# layout.net
KiCad netlist of a schematic drawn in EAGLE
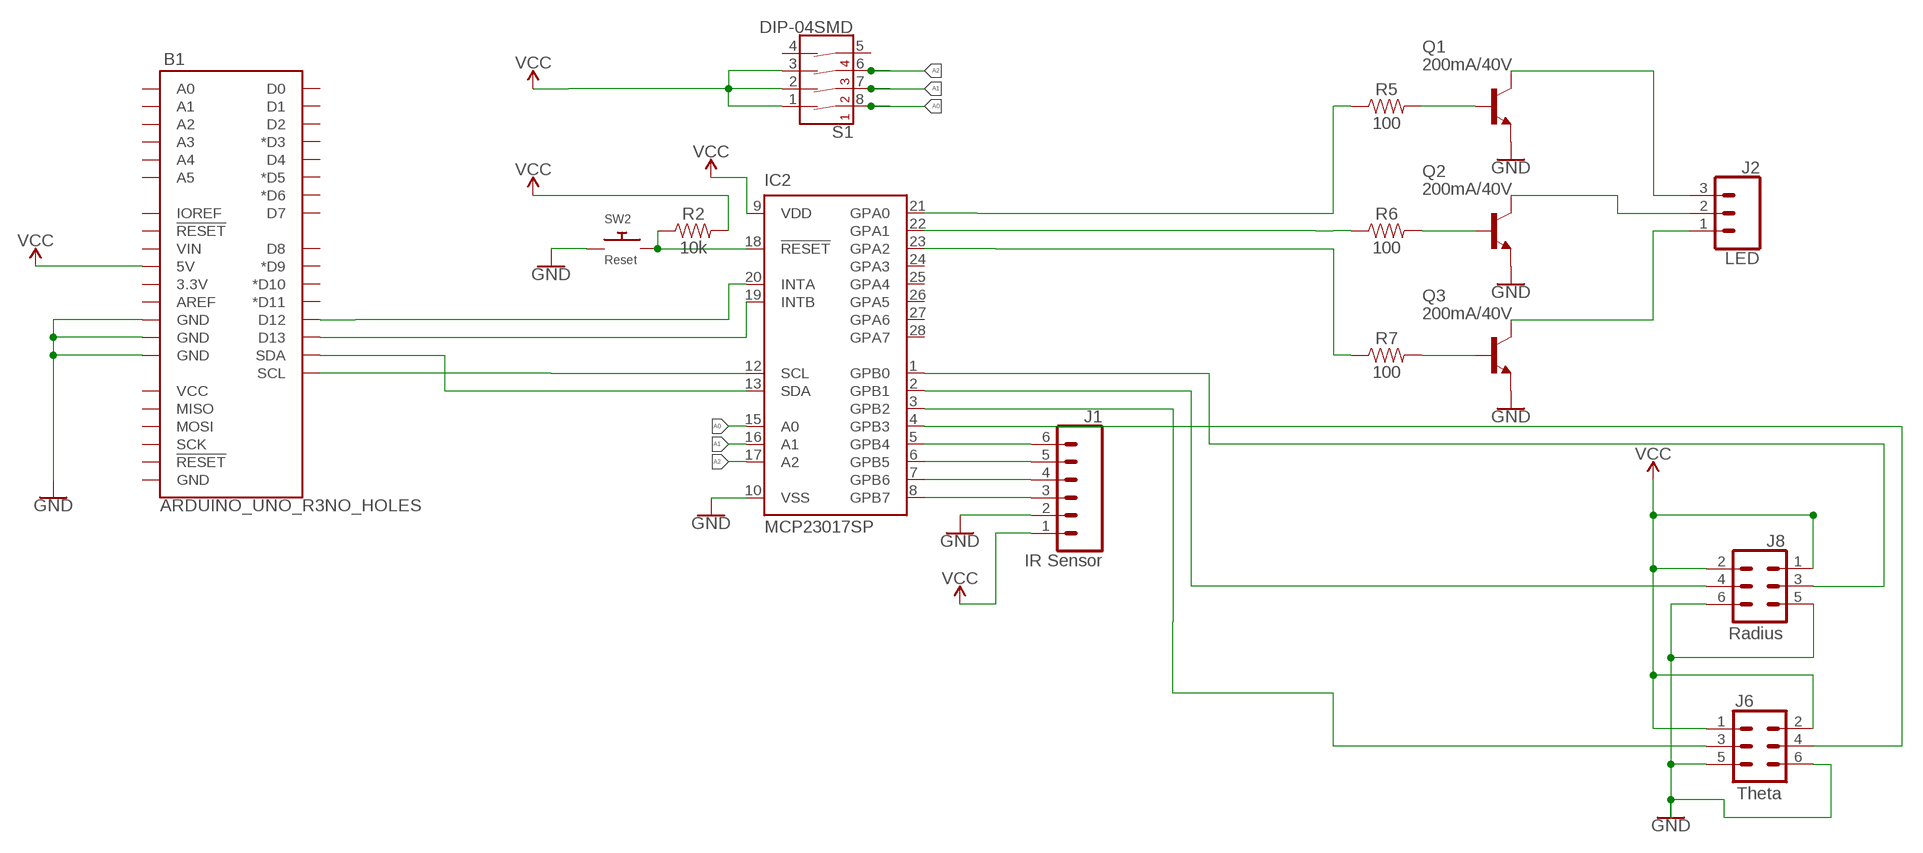
[diagram p0: schematic, sheet 1]

(export (version "E")
  (design (tool "Eeschema 10.0.6"))
  (components
    (comp (ref "B1")
      (value "ARDUINO_UNO_R3NO_HOLES")
      (footprint "eagle-import:ARDUINO_R3_NO_HOLES")
      (libsource (lib "eagle-import") (part "ARDUINO_UNO_R3NO_HOLES"))
    )
    (comp (ref "IC2")
      (value "MCP23017SP")
      (footprint "eagle-import:DIL28-3")
      (libsource (lib "eagle-import") (part "MCP23017SP"))
    )
    (comp (ref "J1")
      (value "IR Sensor")
      (footprint "eagle-import:1X06")
      (libsource (lib "eagle-import") (part "CONN_06SILK_FEMALE_PTH"))
    )
    (comp (ref "J2")
      (value "LED")
      (footprint "eagle-import:1X03")
      (libsource (lib "eagle-import") (part "CONN_03"))
    )
    (comp (ref "J6")
      (value "Theta")
      (footprint "eagle-import:2X3")
      (libsource (lib "eagle-import") (part "CONN_03X22X3_SILK_MALE_PTH"))
    )
    (comp (ref "J8")
      (value "Radius")
      (footprint "eagle-import:2X3")
      (libsource (lib "eagle-import") (part "CONN_03X22X3_SILK_MALE_PTH"))
    )
    (comp (ref "Q1")
      (value "200mA/40V")
      (footprint "eagle-import:TO220")
      (libsource (lib "eagle-import") (part "-NPN-TO220"))
    )
    (comp (ref "Q2")
      (value "200mA/40V")
      (footprint "eagle-import:TO220")
      (libsource (lib "eagle-import") (part "-NPN-TO220"))
    )
    (comp (ref "Q3")
      (value "200mA/40V")
      (footprint "eagle-import:TO220")
      (libsource (lib "eagle-import") (part "-NPN-TO220"))
    )
    (comp (ref "R2")
      (value "10k")
      (footprint "eagle-import:0603")
      (libsource (lib "eagle-import") (part "10KOHM-0603-1/10W-1%"))
    )
    (comp (ref "R5")
      (value "100")
      (footprint "eagle-import:0603")
      (libsource (lib "eagle-import") (part "100OHM-0603-1/4W-5%"))
    )
    (comp (ref "R6")
      (value "100")
      (footprint "eagle-import:0603")
      (libsource (lib "eagle-import") (part "100OHM-0603-1/4W-5%"))
    )
    (comp (ref "R7")
      (value "100")
      (footprint "eagle-import:0603")
      (libsource (lib "eagle-import") (part "100OHM-0603-1/4W-5%"))
    )
    (comp (ref "S1")
      (value "DIP-04SMD")
      (footprint "eagle-import:DIPSWITCH-04-SMD")
      (libsource (lib "eagle-import") (part "DIP-04SMD"))
    )
    (comp (ref "SW2")
      (value "Reset")
      (footprint "eagle-import:BTN_CK_KSS")
      (libsource (lib "eagle-import") (part "SWITCH_PUSHBUTTONC&K_KSS"))
    )
  )
  (nets
    (net (code "1") (name "A0") (class "Default")
      (node (ref "IC2") (pin "15") (pinfunction "A0_15") (pintype "input"))
      (node (ref "S1") (pin "8") (pinfunction "1B_8") (pintype "bidirectional"))
    )
    (net (code "2") (name "A1") (class "Default")
      (node (ref "IC2") (pin "16") (pinfunction "A1_16") (pintype "input"))
      (node (ref "S1") (pin "7") (pinfunction "2B_7") (pintype "bidirectional"))
    )
    (net (code "3") (name "A2") (class "Default")
      (node (ref "IC2") (pin "17") (pinfunction "A2_17") (pintype "input"))
      (node (ref "S1") (pin "6") (pinfunction "3B_6") (pintype "bidirectional"))
    )
    (net (code "4") (name "GND") (class "Default")
      (node (ref "B1") (pin "GND@2") (pinfunction "GND_GND@2") (pintype "bidirectional"))
      (node (ref "B1") (pin "GND@3") (pinfunction "GND_GND@3") (pintype "bidirectional"))
      (node (ref "B1") (pin "GND@4") (pinfunction "GND_GND@4") (pintype "bidirectional"))
      (node (ref "IC2") (pin "10") (pinfunction "VSS_10") (pintype "power_in"))
      (node (ref "J1") (pin "2") (pinfunction "2_2") (pintype "passive"))
      (node (ref "J6") (pin "5") (pinfunction "5_5") (pintype "bidirectional"))
      (node (ref "J6") (pin "6") (pinfunction "6_6") (pintype "bidirectional"))
      (node (ref "J8") (pin "5") (pinfunction "5_5") (pintype "bidirectional"))
      (node (ref "J8") (pin "6") (pinfunction "6_6") (pintype "bidirectional"))
      (node (ref "Q1") (pin "3") (pinfunction "E_3") (pintype "passive"))
      (node (ref "Q2") (pin "3") (pinfunction "E_3") (pintype "passive"))
      (node (ref "Q3") (pin "3") (pinfunction "E_3") (pintype "passive"))
      (node (ref "SW2") (pin "P$1") (pinfunction "P$1_P$1") (pintype "passive"))
    )
    (net (code "5") (name "Net-(IC2-GPA0)") (class "Default")
      (node (ref "IC2") (pin "21") (pinfunction "GPA0_21") (pintype "bidirectional"))
      (node (ref "R5") (pin "1") (pinfunction "1_1") (pintype "passive"))
    )
    (net (code "6") (name "Net-(IC2-GPA1)") (class "Default")
      (node (ref "IC2") (pin "22") (pinfunction "GPA1_22") (pintype "bidirectional"))
      (node (ref "R6") (pin "1") (pinfunction "1_1") (pintype "passive"))
    )
    (net (code "7") (name "Net-(IC2-GPA2)") (class "Default")
      (node (ref "IC2") (pin "23") (pinfunction "GPA2_23") (pintype "bidirectional"))
      (node (ref "R7") (pin "1") (pinfunction "1_1") (pintype "passive"))
    )
    (net (code "8") (name "Net-(IC2-GPB0)") (class "Default")
      (node (ref "IC2") (pin "1") (pinfunction "GPB0_1") (pintype "bidirectional"))
      (node (ref "J8") (pin "3") (pinfunction "3_3") (pintype "bidirectional"))
    )
    (net (code "9") (name "Net-(IC2-GPB1)") (class "Default")
      (node (ref "IC2") (pin "2") (pinfunction "GPB1_2") (pintype "bidirectional"))
      (node (ref "J8") (pin "4") (pinfunction "4_4") (pintype "bidirectional"))
    )
    (net (code "10") (name "Net-(IC2-GPB2)") (class "Default")
      (node (ref "IC2") (pin "3") (pinfunction "GPB2_3") (pintype "bidirectional"))
      (node (ref "J6") (pin "3") (pinfunction "3_3") (pintype "bidirectional"))
    )
    (net (code "11") (name "Net-(IC2-GPB3)") (class "Default")
      (node (ref "IC2") (pin "4") (pinfunction "GPB3_4") (pintype "bidirectional"))
      (node (ref "J6") (pin "4") (pinfunction "4_4") (pintype "bidirectional"))
    )
    (net (code "12") (name "Net-(IC2-GPB4)") (class "Default")
      (node (ref "IC2") (pin "5") (pinfunction "GPB4_5") (pintype "bidirectional"))
      (node (ref "J1") (pin "6") (pinfunction "6_6") (pintype "passive"))
    )
    (net (code "13") (name "Net-(IC2-GPB5)") (class "Default")
      (node (ref "IC2") (pin "6") (pinfunction "GPB5_6") (pintype "bidirectional"))
      (node (ref "J1") (pin "5") (pinfunction "5_5") (pintype "passive"))
    )
    (net (code "14") (name "Net-(IC2-GPB6)") (class "Default")
      (node (ref "IC2") (pin "7") (pinfunction "GPB6_7") (pintype "bidirectional"))
      (node (ref "J1") (pin "4") (pinfunction "4_4") (pintype "passive"))
    )
    (net (code "15") (name "Net-(IC2-GPB7)") (class "Default")
      (node (ref "IC2") (pin "8") (pinfunction "GPB7_8") (pintype "bidirectional"))
      (node (ref "J1") (pin "3") (pinfunction "3_3") (pintype "passive"))
    )
    (net (code "16") (name "Net-(IC2-INTA)") (class "Default")
      (node (ref "B1") (pin "D12") (pinfunction "D12_D12") (pintype "bidirectional"))
      (node (ref "IC2") (pin "20") (pinfunction "INTA_20") (pintype "output"))
    )
    (net (code "17") (name "Net-(IC2-INTB)") (class "Default")
      (node (ref "B1") (pin "D13") (pinfunction "D13_D13") (pintype "bidirectional"))
      (node (ref "IC2") (pin "19") (pinfunction "INTB_19") (pintype "output"))
    )
    (net (code "18") (name "Net-(IC2-SCL)") (class "Default")
      (node (ref "B1") (pin "SCL") (pinfunction "SCL_SCL") (pintype "bidirectional"))
      (node (ref "IC2") (pin "12") (pinfunction "SCL_12") (pintype "input"))
    )
    (net (code "19") (name "Net-(IC2-SDA)") (class "Default")
      (node (ref "B1") (pin "SDA") (pinfunction "SDA_SDA") (pintype "bidirectional"))
      (node (ref "IC2") (pin "13") (pinfunction "SDA_13") (pintype "bidirectional"))
    )
    (net (code "20") (name "Net-(IC2-~{RESET})") (class "Default")
      (node (ref "IC2") (pin "18") (pinfunction "~{RESET}_18") (pintype "input"))
      (node (ref "R2") (pin "1") (pinfunction "1_1") (pintype "passive"))
      (node (ref "SW2") (pin "P$2") (pinfunction "P$2_P$2") (pintype "passive"))
    )
    (net (code "21") (name "Net-(Q1-B)") (class "Default")
      (node (ref "Q1") (pin "1") (pinfunction "B_1") (pintype "passive"))
      (node (ref "R5") (pin "2") (pinfunction "2_2") (pintype "passive"))
    )
    (net (code "22") (name "Net-(Q1-C)") (class "Default")
      (node (ref "J2") (pin "3") (pinfunction "3_3") (pintype "passive"))
      (node (ref "Q1") (pin "2") (pinfunction "C_2") (pintype "passive"))
    )
    (net (code "23") (name "Net-(Q2-B)") (class "Default")
      (node (ref "Q2") (pin "1") (pinfunction "B_1") (pintype "passive"))
      (node (ref "R6") (pin "2") (pinfunction "2_2") (pintype "passive"))
    )
    (net (code "24") (name "Net-(Q2-C)") (class "Default")
      (node (ref "J2") (pin "2") (pinfunction "2_2") (pintype "passive"))
      (node (ref "Q2") (pin "2") (pinfunction "C_2") (pintype "passive"))
    )
    (net (code "25") (name "Net-(Q3-B)") (class "Default")
      (node (ref "Q3") (pin "1") (pinfunction "B_1") (pintype "passive"))
      (node (ref "R7") (pin "2") (pinfunction "2_2") (pintype "passive"))
    )
    (net (code "26") (name "Net-(Q3-C)") (class "Default")
      (node (ref "J2") (pin "1") (pinfunction "1_1") (pintype "passive"))
      (node (ref "Q3") (pin "2") (pinfunction "C_2") (pintype "passive"))
    )
    (net (code "27") (name "VCC") (class "Default")
      (node (ref "B1") (pin "5V") (pinfunction "5V_5V") (pintype "bidirectional"))
      (node (ref "IC2") (pin "9") (pinfunction "VDD_9") (pintype "power_in"))
      (node (ref "J1") (pin "1") (pinfunction "1_1") (pintype "passive"))
      (node (ref "J6") (pin "1") (pinfunction "1_1") (pintype "bidirectional"))
      (node (ref "J6") (pin "2") (pinfunction "2_2") (pintype "bidirectional"))
      (node (ref "J8") (pin "1") (pinfunction "1_1") (pintype "bidirectional"))
      (node (ref "J8") (pin "2") (pinfunction "2_2") (pintype "bidirectional"))
      (node (ref "R2") (pin "2") (pinfunction "2_2") (pintype "passive"))
      (node (ref "S1") (pin "1") (pinfunction "1A_1") (pintype "bidirectional"))
      (node (ref "S1") (pin "2") (pinfunction "2A_2") (pintype "bidirectional"))
      (node (ref "S1") (pin "3") (pinfunction "3A_3") (pintype "bidirectional"))
    )
    (net (code "28") (name "unconnected-(B1-*D3-PadD3)") (class "Default")
      (node (ref "B1") (pin "D3") (pinfunction "*D3_D3") (pintype "bidirectional"))
    )
    (net (code "29") (name "unconnected-(B1-*D5-PadD5)") (class "Default")
      (node (ref "B1") (pin "D5") (pinfunction "*D5_D5") (pintype "bidirectional"))
    )
    (net (code "30") (name "unconnected-(B1-*D6-PadD6)") (class "Default")
      (node (ref "B1") (pin "D6") (pinfunction "*D6_D6") (pintype "bidirectional"))
    )
    (net (code "31") (name "unconnected-(B1-*D9-PadD9)") (class "Default")
      (node (ref "B1") (pin "D9") (pinfunction "*D9_D9") (pintype "bidirectional"))
    )
    (net (code "32") (name "unconnected-(B1-*D10-PadD10)") (class "Default")
      (node (ref "B1") (pin "D10") (pinfunction "*D10_D10") (pintype "bidirectional"))
    )
    (net (code "33") (name "unconnected-(B1-*D11-PadD11)") (class "Default")
      (node (ref "B1") (pin "D11") (pinfunction "*D11_D11") (pintype "bidirectional"))
    )
    (net (code "34") (name "unconnected-(B1-GND-PadGND@1)") (class "Default")
      (node (ref "B1") (pin "GND@1") (pinfunction "GND_GND@1") (pintype "bidirectional"))
    )
    (net (code "35") (name "unconnected-(B1-Pad3.3V)") (class "Default")
      (node (ref "B1") (pin "3.3V") (pinfunction "3.3V_3.3V") (pintype "bidirectional"))
    )
    (net (code "36") (name "unconnected-(B1-PadA0)") (class "Default")
      (node (ref "B1") (pin "A0") (pinfunction "A0_A0") (pintype "bidirectional"))
    )
    (net (code "37") (name "unconnected-(B1-PadA1)") (class "Default")
      (node (ref "B1") (pin "A1") (pinfunction "A1_A1") (pintype "bidirectional"))
    )
    (net (code "38") (name "unconnected-(B1-PadA2)") (class "Default")
      (node (ref "B1") (pin "A2") (pinfunction "A2_A2") (pintype "bidirectional"))
    )
    (net (code "39") (name "unconnected-(B1-PadA3)") (class "Default")
      (node (ref "B1") (pin "A3") (pinfunction "A3_A3") (pintype "bidirectional"))
    )
    (net (code "40") (name "unconnected-(B1-PadA4)") (class "Default")
      (node (ref "B1") (pin "A4") (pinfunction "A4_A4") (pintype "bidirectional"))
    )
    (net (code "41") (name "unconnected-(B1-PadA5)") (class "Default")
      (node (ref "B1") (pin "A5") (pinfunction "A5_A5") (pintype "bidirectional"))
    )
    (net (code "42") (name "unconnected-(B1-PadAREF)") (class "Default")
      (node (ref "B1") (pin "AREF") (pinfunction "AREF_AREF") (pintype "bidirectional"))
    )
    (net (code "43") (name "unconnected-(B1-PadD0)") (class "Default")
      (node (ref "B1") (pin "D0") (pinfunction "D0_D0") (pintype "bidirectional"))
    )
    (net (code "44") (name "unconnected-(B1-PadD1)") (class "Default")
      (node (ref "B1") (pin "D1") (pinfunction "D1_D1") (pintype "bidirectional"))
    )
    (net (code "45") (name "unconnected-(B1-PadD2)") (class "Default")
      (node (ref "B1") (pin "D2") (pinfunction "D2_D2") (pintype "bidirectional"))
    )
    (net (code "46") (name "unconnected-(B1-PadD4)") (class "Default")
      (node (ref "B1") (pin "D4") (pinfunction "D4_D4") (pintype "bidirectional"))
    )
    (net (code "47") (name "unconnected-(B1-PadD7)") (class "Default")
      (node (ref "B1") (pin "D7") (pinfunction "D7_D7") (pintype "bidirectional"))
    )
    (net (code "48") (name "unconnected-(B1-PadD8)") (class "Default")
      (node (ref "B1") (pin "D8") (pinfunction "D8_D8") (pintype "bidirectional"))
    )
    (net (code "49") (name "unconnected-(B1-PadIOREF)") (class "Default")
      (node (ref "B1") (pin "IOREF") (pinfunction "IOREF_IOREF") (pintype "bidirectional"))
    )
    (net (code "50") (name "unconnected-(B1-PadMISO)") (class "Default")
      (node (ref "B1") (pin "MISO") (pinfunction "MISO_MISO") (pintype "bidirectional"))
    )
    (net (code "51") (name "unconnected-(B1-PadMOSI)") (class "Default")
      (node (ref "B1") (pin "MOSI") (pinfunction "MOSI_MOSI") (pintype "bidirectional"))
    )
    (net (code "52") (name "unconnected-(B1-PadSCK)") (class "Default")
      (node (ref "B1") (pin "SCK") (pinfunction "SCK_SCK") (pintype "bidirectional"))
    )
    (net (code "53") (name "unconnected-(B1-PadVCC)") (class "Default")
      (node (ref "B1") (pin "VCC") (pinfunction "VCC_VCC") (pintype "bidirectional"))
    )
    (net (code "54") (name "unconnected-(B1-PadVIN)") (class "Default")
      (node (ref "B1") (pin "VIN") (pinfunction "VIN_VIN") (pintype "bidirectional"))
    )
    (net (code "55") (name "unconnected-(B1-~{RESET}-PadRESET@1)") (class "Default")
      (node (ref "B1") (pin "RESET@1") (pinfunction "~{RESET}_RESET@1") (pintype "bidirectional"))
    )
    (net (code "56") (name "unconnected-(B1-~{RESET}-PadRESET@2)") (class "Default")
      (node (ref "B1") (pin "RESET@2") (pinfunction "~{RESET}_RESET@2") (pintype "bidirectional"))
    )
    (net (code "57") (name "unconnected-(IC2-GPA3-Pad24)") (class "Default")
      (node (ref "IC2") (pin "24") (pinfunction "GPA3_24") (pintype "bidirectional"))
    )
    (net (code "58") (name "unconnected-(IC2-GPA4-Pad25)") (class "Default")
      (node (ref "IC2") (pin "25") (pinfunction "GPA4_25") (pintype "bidirectional"))
    )
    (net (code "59") (name "unconnected-(IC2-GPA5-Pad26)") (class "Default")
      (node (ref "IC2") (pin "26") (pinfunction "GPA5_26") (pintype "bidirectional"))
    )
    (net (code "60") (name "unconnected-(IC2-GPA6-Pad27)") (class "Default")
      (node (ref "IC2") (pin "27") (pinfunction "GPA6_27") (pintype "bidirectional"))
    )
    (net (code "61") (name "unconnected-(IC2-GPA7-Pad28)") (class "Default")
      (node (ref "IC2") (pin "28") (pinfunction "GPA7_28") (pintype "bidirectional"))
    )
    (net (code "62") (name "unconnected-(S1-4A-Pad4)") (class "Default")
      (node (ref "S1") (pin "4") (pinfunction "4A_4") (pintype "bidirectional"))
    )
    (net (code "63") (name "unconnected-(S1-4B-Pad5)") (class "Default")
      (node (ref "S1") (pin "5") (pinfunction "4B_5") (pintype "bidirectional"))
    )
  )
)
